# USB.net
KiCad netlist of a schematic drawn in Altium Designer
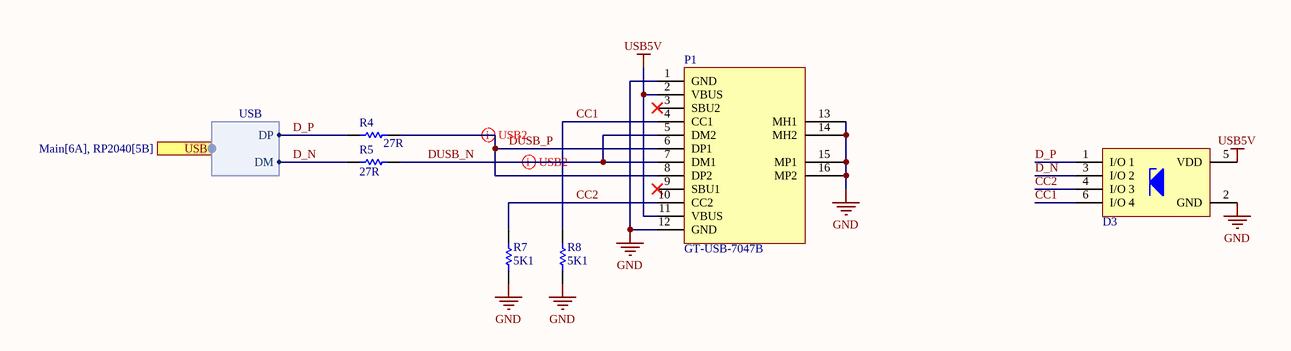
[diagram p0: USB.SchDoc]

(export (version "E")
  (design (tool "Eeschema 10.0.6"))
  (components
    (comp (ref "D3")
      (value "3.3V")
      (footprint "WE-TVS_SOT23-6L")
      (description "WE-TVS TVS Diode – High Speed Series, SOT23-6L, 4+1 Channel, 3.3V, 2pF")
      (fields
        (field (name "MANUFACTURER PART NUMBER") "824015043")
        (field (name "MANUFACTURER") "Wurth Elektronik")
      )
      (libsource (lib "Altium_WE-TVS (rev22b)") (part "824015043"))
    )
    (comp (ref "P1")
      (value "GT-USB-7047B")
      (footprint "GT-USB-7047B")
      (libsource (lib "Custom Components") (part "GT-USB-7047B"))
    )
    (comp (ref "R4")
      (value "27R")
      (footprint "Custom Components:0402 resistor")
      (libsource (lib "Custom Components") (part "Resistor 0402 1K"))
    )
    (comp (ref "R5")
      (value "27R")
      (footprint "Custom Components:0402 resistor")
      (libsource (lib "Custom Components") (part "Resistor 0402 1K"))
    )
    (comp (ref "R7")
      (value "5K1")
      (footprint "Custom Components:0402 resistor")
      (libsource (lib "Custom Components") (part "Resistor 0402 1K"))
    )
    (comp (ref "R8")
      (value "5K1")
      (footprint "Custom Components:0402 resistor")
      (libsource (lib "Custom Components") (part "Resistor 0402 1K"))
    )
  )
  (nets
    (net (code "2") (name "/CC1") (class "Default")
      (node (ref "D3") (pin "6") (pinfunction "I/O_4_6") (pintype "passive"))
      (node (ref "P1") (pin "4") (pinfunction "CC1_4") (pintype "passive"))
      (node (ref "R8") (pin "2") (pinfunction "2_2") (pintype "passive"))
    )
    (net (code "3") (name "/CC2") (class "Default")
      (node (ref "D3") (pin "4") (pinfunction "I/O_3_4") (pintype "passive"))
      (node (ref "P1") (pin "10") (pinfunction "CC2_10") (pintype "passive"))
      (node (ref "R7") (pin "2") (pinfunction "2_2") (pintype "passive"))
    )
    (net (code "4") (name "/DUSB_N") (class "Default")
      (node (ref "P1") (pin "5") (pinfunction "DM2_5") (pintype "passive"))
      (node (ref "P1") (pin "7") (pinfunction "DM1_7") (pintype "passive"))
      (node (ref "R5") (pin "1") (pinfunction "1_1") (pintype "passive"))
    )
    (net (code "5") (name "/DUSB_P") (class "Default")
      (node (ref "P1") (pin "6") (pinfunction "DP1_6") (pintype "passive"))
      (node (ref "P1") (pin "8") (pinfunction "DP2_8") (pintype "passive"))
      (node (ref "R4") (pin "1") (pinfunction "1_1") (pintype "passive"))
    )
    (net (code "6") (name "/D_N") (class "Default")
      (node (ref "D3") (pin "3") (pinfunction "I/O_2_3") (pintype "passive"))
      (node (ref "R5") (pin "2") (pinfunction "2_2") (pintype "passive"))
    )
    (net (code "7") (name "/D_P") (class "Default")
      (node (ref "D3") (pin "1") (pinfunction "I/O_1_1") (pintype "passive"))
      (node (ref "R4") (pin "2") (pinfunction "2_2") (pintype "passive"))
    )
    (net (code "9") (name "GND") (class "Default")
      (node (ref "D3") (pin "2") (pinfunction "GND_2") (pintype "passive"))
      (node (ref "P1") (pin "1") (pinfunction "GND_1") (pintype "passive"))
      (node (ref "P1") (pin "12") (pinfunction "GND_12") (pintype "passive"))
      (node (ref "P1") (pin "13") (pinfunction "MH1_13") (pintype "passive"))
      (node (ref "P1") (pin "14") (pinfunction "MH2_14") (pintype "passive"))
      (node (ref "P1") (pin "15") (pinfunction "MP1_15") (pintype "passive"))
      (node (ref "P1") (pin "16") (pinfunction "MP2_16") (pintype "passive"))
      (node (ref "R7") (pin "1") (pinfunction "1_1") (pintype "passive"))
      (node (ref "R8") (pin "1") (pinfunction "1_1") (pintype "passive"))
    )
    (net (code "10") (name "USB5V") (class "Default")
      (node (ref "D3") (pin "5") (pinfunction "VDD_5") (pintype "passive"))
      (node (ref "P1") (pin "11") (pinfunction "VBUS_11") (pintype "passive"))
      (node (ref "P1") (pin "2") (pinfunction "VBUS_2") (pintype "passive"))
    )
    (net (code "11") (name "unconnected-(P1-SBU1-Pad9)") (class "Default")
      (node (ref "P1") (pin "9") (pinfunction "SBU1_9") (pintype "passive+no_connect"))
    )
    (net (code "12") (name "unconnected-(P1-SBU2-Pad3)") (class "Default")
      (node (ref "P1") (pin "3") (pinfunction "SBU2_3") (pintype "passive+no_connect"))
    )
  )
)
